# WallE_2_0.net
KiCad netlist of a schematic drawn in EAGLE
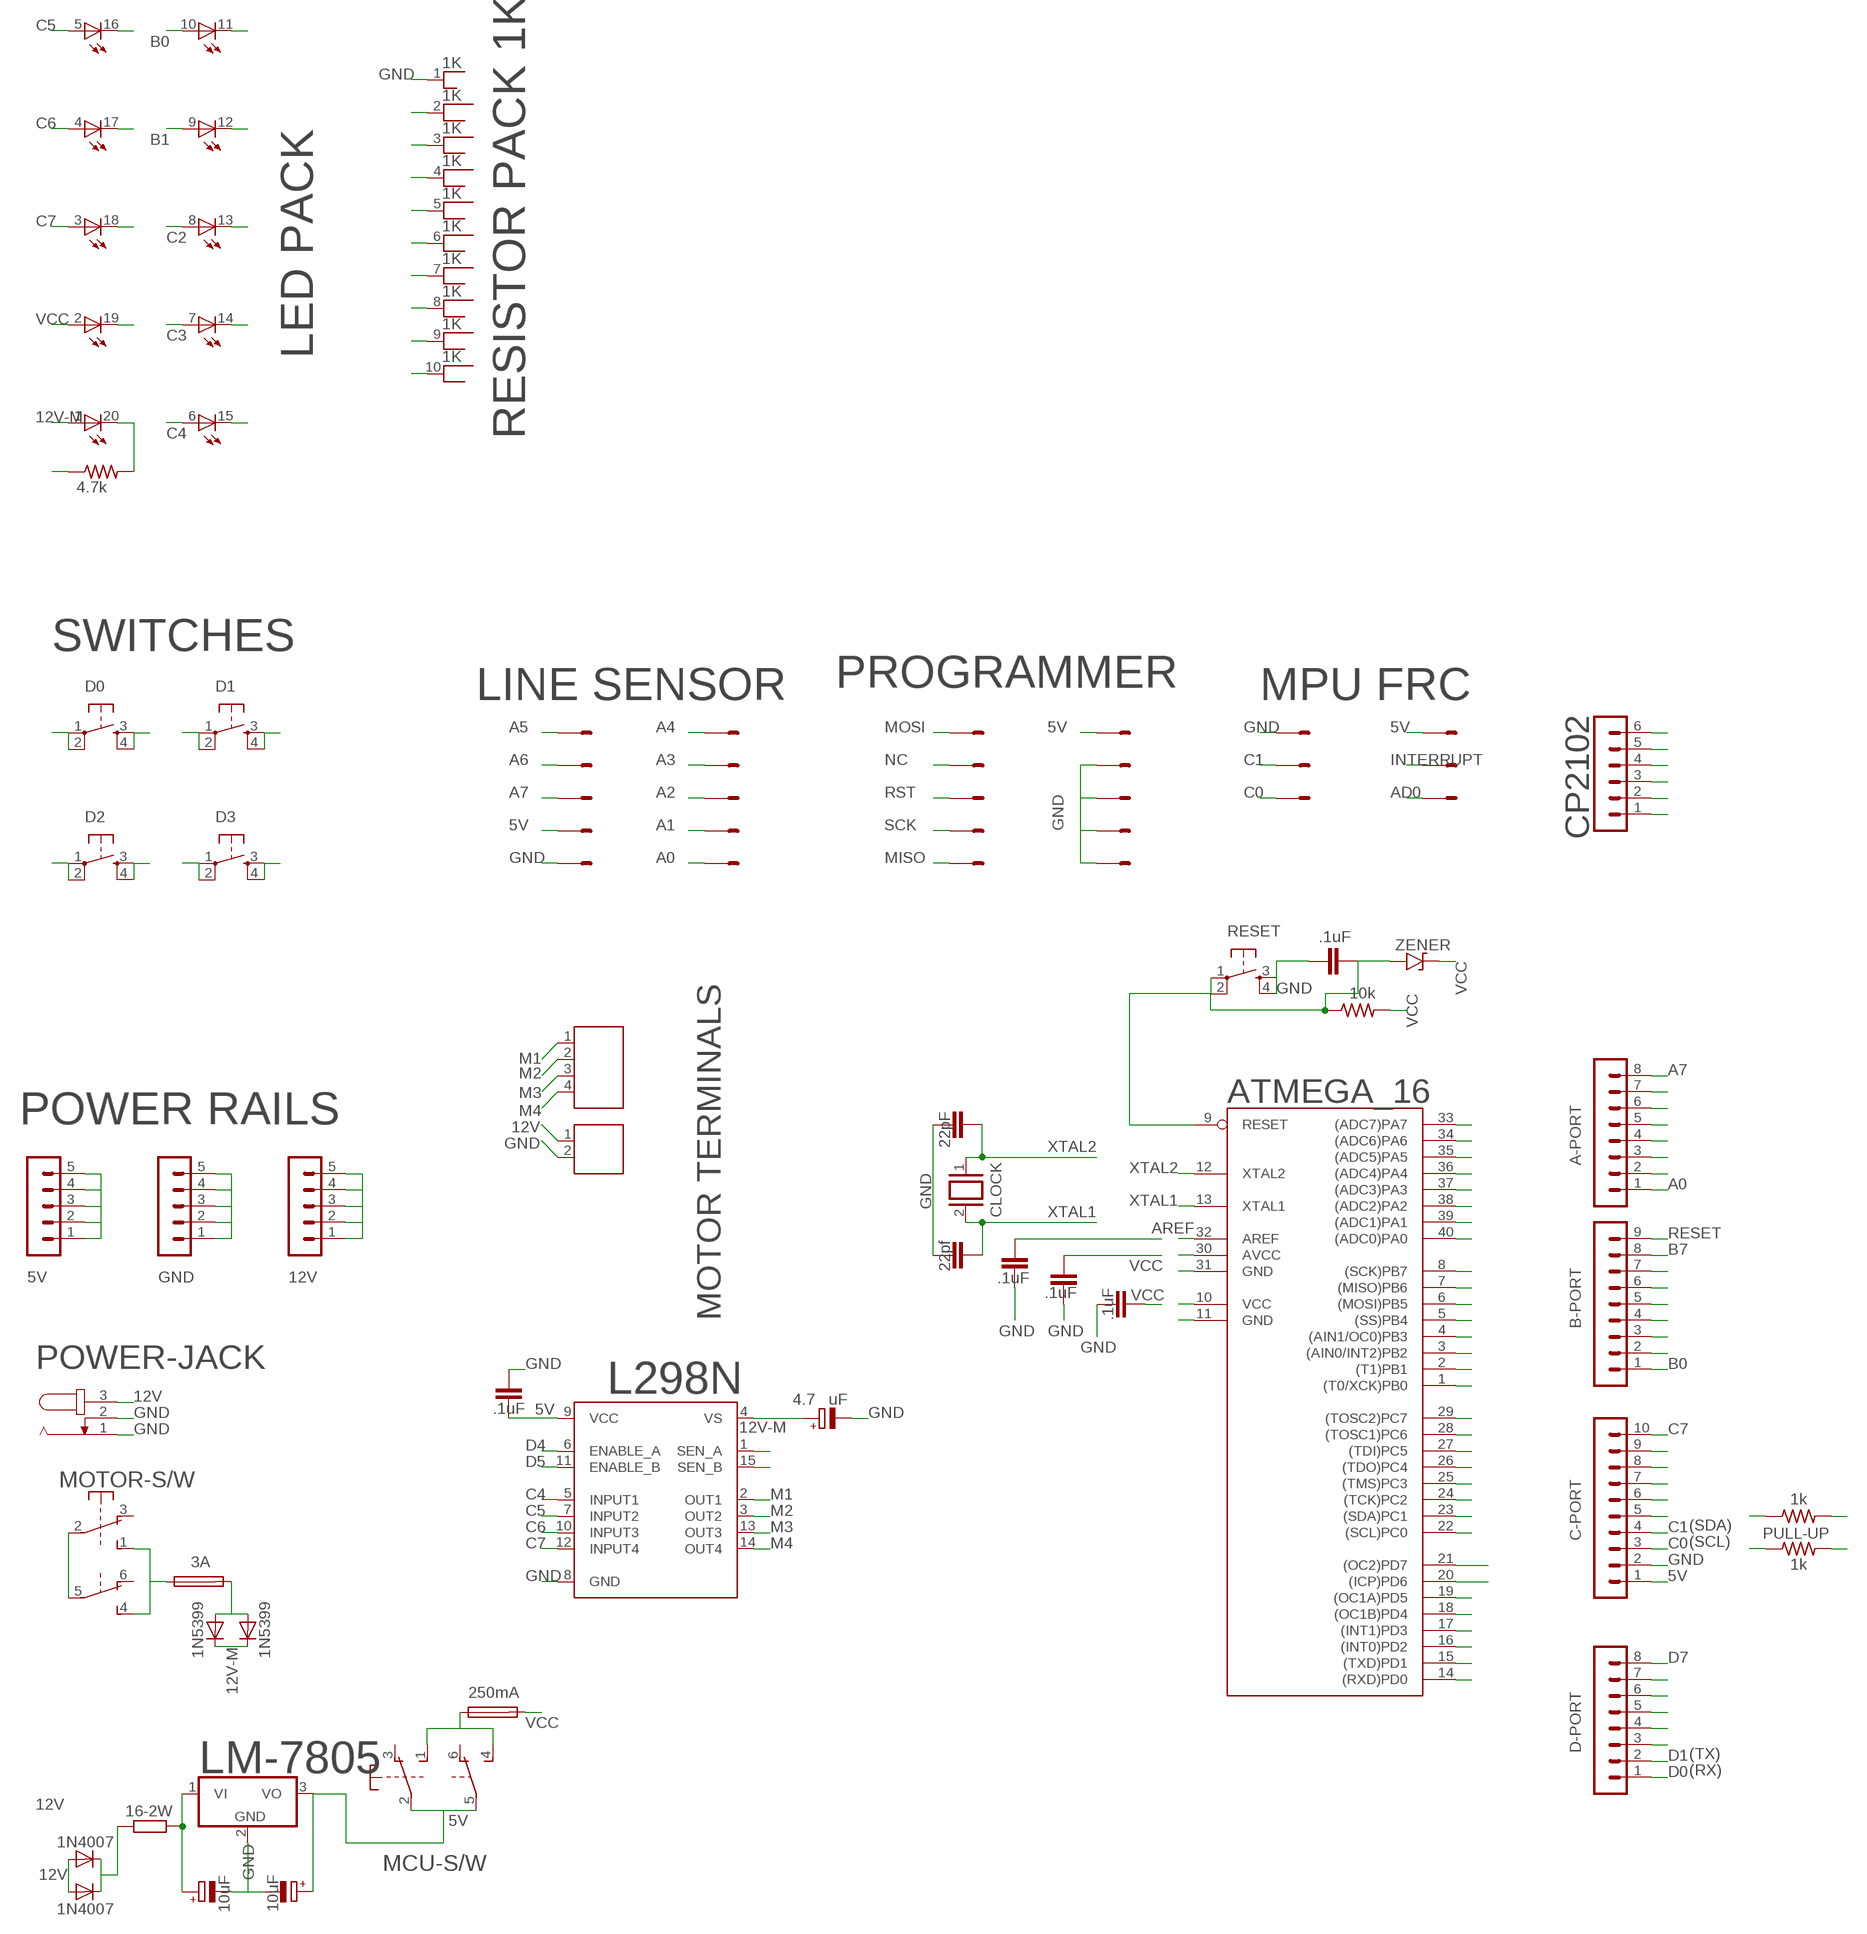
[diagram p0: schematic, sheet 1]

(export (version "E")
  (design (tool "Eeschema 10.0.6"))
  (components
    (comp (ref "5V")
      (value "MA05-1")
      (footprint "eagle-import:MA05-1")
      (libsource (lib "eagle-import") (part "MA05-1"))
    )
    (comp (ref "12V")
      (value "MA05-1")
      (footprint "eagle-import:MA05-1")
      (libsource (lib "eagle-import") (part "MA05-1"))
    )
    (comp (ref "16-2W")
      (value "R-EU_0617/17")
      (footprint "eagle-import:0617_17")
      (libsource (lib "eagle-import") (part "R-EU_0617/17"))
    )
    (comp (ref "A-PORT")
      (value "MA08-1")
      (footprint "eagle-import:MA08-1")
      (libsource (lib "eagle-import") (part "MA08-1"))
    )
    (comp (ref "ATMEGA_16")
      (value "MEGA32-P")
      (footprint "eagle-import:DIL40")
      (fields (field (name "MPN") "ATMEGA32-16PU"))
      (libsource (lib "eagle-import") (part "MEGA32-P"))
    )
    (comp (ref "B-PORT")
      (value "MA09-1")
      (footprint "eagle-import:MA09-1")
      (libsource (lib "eagle-import") (part "MA09-1"))
    )
    (comp (ref "C-PORT")
      (value "MA10-1")
      (footprint "eagle-import:MA10-1")
      (libsource (lib "eagle-import") (part "MA10-1"))
    )
    (comp (ref "C1")
      (value "10uF")
      (footprint "eagle-import:E2,5-6")
      (libsource (lib "eagle-import") (part "CPOL-EUE2.5-6"))
    )
    (comp (ref "C2")
      (value ".1uF")
      (footprint "eagle-import:C5B2.5")
      (libsource (lib "eagle-import") (part "C5/2.5"))
    )
    (comp (ref "C3")
      (value "22pf")
      (footprint "eagle-import:C2.5-2")
      (libsource (lib "eagle-import") (part "C2.5/2"))
    )
    (comp (ref "C4")
      (value "22pF")
      (footprint "eagle-import:C2.5-2")
      (libsource (lib "eagle-import") (part "C2.5/2"))
    )
    (comp (ref "C5")
      (value ".1uF")
      (footprint "eagle-import:C5B2.5")
      (libsource (lib "eagle-import") (part "C5/2.5"))
    )
    (comp (ref "C6")
      (value ".1uF")
      (footprint "eagle-import:C5B2.5")
      (libsource (lib "eagle-import") (part "C5/2.5"))
    )
    (comp (ref "C7")
      (value ".1uF")
      (footprint "eagle-import:C5B2.5")
      (libsource (lib "eagle-import") (part "C5/2.5"))
    )
    (comp (ref "C8")
      (value "4.7 uF")
      (footprint "eagle-import:E2,5-6")
      (libsource (lib "eagle-import") (part "CPOL-EUE2.5-6"))
    )
    (comp (ref "C9")
      (value ".1uF")
      (footprint "eagle-import:C5B2.5")
      (libsource (lib "eagle-import") (part "C5/2.5"))
    )
    (comp (ref "C10")
      (value "10uF")
      (footprint "eagle-import:E2,5-6")
      (libsource (lib "eagle-import") (part "CPOL-EUE2.5-6"))
    )
    (comp (ref "CLOCK")
      (value "XTAL/S")
      (footprint "eagle-import:QS")
      (libsource (lib "eagle-import") (part "XTAL/S"))
    )
    (comp (ref "CP2102")
      (value "MA06-1")
      (footprint "eagle-import:MA06-1")
      (libsource (lib "eagle-import") (part "MA06-1"))
    )
    (comp (ref "D-PORT")
      (value "MA08-1")
      (footprint "eagle-import:MA08-1")
      (libsource (lib "eagle-import") (part "MA08-1"))
    )
    (comp (ref "D0")
      (value "DTS-6")
      (footprint "eagle-import:DTS-6")
      (libsource (lib "eagle-import") (part "DTS-6"))
    )
    (comp (ref "D1")
      (value "DTS-6")
      (footprint "eagle-import:DTS-6")
      (libsource (lib "eagle-import") (part "DTS-6"))
    )
    (comp (ref "D2")
      (value "DTS-6")
      (footprint "eagle-import:DTS-6")
      (libsource (lib "eagle-import") (part "DTS-6"))
    )
    (comp (ref "D3")
      (value "DTS-6")
      (footprint "eagle-import:DTS-6")
      (libsource (lib "eagle-import") (part "DTS-6"))
    )
    (comp (ref "D4")
      (value "1N4007")
      (footprint "eagle-import:D-7.5")
      (libsource (lib "eagle-import") (part "DIODE-D-7.5"))
    )
    (comp (ref "D5")
      (value "1N4007")
      (footprint "eagle-import:D-7.5")
      (libsource (lib "eagle-import") (part "DIODE-D-7.5"))
    )
    (comp (ref "D6")
      (value "1N5399")
      (footprint "eagle-import:DO15-12")
      (libsource (lib "eagle-import") (part "DIODE-DO15-12"))
    )
    (comp (ref "D7")
      (value "1N5399")
      (footprint "eagle-import:DO15-12")
      (libsource (lib "eagle-import") (part "DIODE-DO15-12"))
    )
    (comp (ref "DZ1")
      (value "LB10")
      (footprint "eagle-import:LB10")
      (libsource (lib "eagle-import") (part "LB10"))
    )
    (comp (ref "F1")
      (value "3A")
      (footprint "eagle-import:SH25")
      (fields (field (name "MF") "SCHURTER") (field (name "MPN") "0031.8211"))
      (libsource (lib "eagle-import") (part "SH25"))
    )
    (comp (ref "F2")
      (value "250mA")
      (footprint "eagle-import:SH25")
      (fields (field (name "MF") "SCHURTER") (field (name "MPN") "0031.8211"))
      (libsource (lib "eagle-import") (part "SH25"))
    )
    (comp (ref "GND")
      (value "MA05-1")
      (footprint "eagle-import:MA05-1")
      (libsource (lib "eagle-import") (part "MA05-1"))
    )
    (comp (ref "J1")
      (value "691131710004")
      (footprint "eagle-import:691131710004")
      (libsource (lib "eagle-import") (part "691131710004"))
    )
    (comp (ref "J2")
      (value "691131710002")
      (footprint "eagle-import:691131710002")
      (libsource (lib "eagle-import") (part "691131710002"))
    )
    (comp (ref "L298N")
      (value "L298")
      (footprint "eagle-import:MULTIWATT-15")
      (fields (field (name "MPN") "L298N"))
      (libsource (lib "eagle-import") (part "L298"))
    )
    (comp (ref "LINE-SENSOR")
      (value "057-010-1")
      (footprint "eagle-import:057-010-1")
      (libsource (lib "eagle-import") (part "057-010-1"))
    )
    (comp (ref "LM-7805")
      (value "786TV")
      (footprint "eagle-import:TO220V")
      (libsource (lib "eagle-import") (part "78TV6"))
    )
    (comp (ref "MCU-S/W")
      (value "9077-2")
      (footprint "eagle-import:9077-2")
      (libsource (lib "eagle-import") (part "9077-2"))
    )
    (comp (ref "MOTOR-S/W")
      (value "9077-2")
      (footprint "eagle-import:9077-2")
      (libsource (lib "eagle-import") (part "9077-2"))
    )
    (comp (ref "MPU-6050")
      (value "057-006-1")
      (footprint "eagle-import:057-006-1")
      (libsource (lib "eagle-import") (part "057-006-1"))
    )
    (comp (ref "POWER-JACK")
      (value "JACK-PLUG1")
      (footprint "eagle-import:SPC4078")
      (libsource (lib "eagle-import") (part "JACK-PLUG1"))
    )
    (comp (ref "R2")
      (value "4.7k")
      (footprint "eagle-import:0207_7")
      (libsource (lib "eagle-import") (part "R-US_0207/7"))
    )
    (comp (ref "R3")
      (value "10k")
      (footprint "eagle-import:0207_7")
      (libsource (lib "eagle-import") (part "R-US_0207/7"))
    )
    (comp (ref "R5")
      (value "1k")
      (footprint "eagle-import:0207_7")
      (libsource (lib "eagle-import") (part "R-US_0207/7"))
    )
    (comp (ref "R6")
      (value "1k")
      (footprint "eagle-import:0207_7")
      (libsource (lib "eagle-import") (part "R-US_0207/7"))
    )
    (comp (ref "RESET")
      (value "DTS-6")
      (footprint "eagle-import:DTS-6")
      (libsource (lib "eagle-import") (part "DTS-6"))
    )
    (comp (ref "RN1")
      (value "1K")
      (footprint "eagle-import:RN-10")
      (libsource (lib "eagle-import") (part "RNX9"))
    )
    (comp (ref "X2")
      (value "PROGRAMMER")
      (footprint "eagle-import:057-010-1")
      (libsource (lib "eagle-import") (part "057-010-1"))
    )
    (comp (ref "ZENER")
      (value "ZENER")
      (footprint "eagle-import:DO35-2")
      (libsource (lib "eagle-import") (part "1N9ZENER2"))
    )
  )
  (nets
    (net (code "1") (name "/5V") (class "Default")
      (node (ref "5V") (pin "1") (pinfunction "1_1") (pintype "passive"))
      (node (ref "5V") (pin "2") (pinfunction "2_2") (pintype "passive"))
      (node (ref "5V") (pin "3") (pinfunction "3_3") (pintype "passive"))
      (node (ref "5V") (pin "4") (pinfunction "4_4") (pintype "passive"))
      (node (ref "5V") (pin "5") (pinfunction "5_5") (pintype "passive"))
      (node (ref "C-PORT") (pin "1") (pinfunction "1_1") (pintype "passive"))
      (node (ref "C10") (pin "+") (pinfunction "+_+") (pintype "passive"))
      (node (ref "C9") (pin "1") (pinfunction "1_1") (pintype "passive"))
      (node (ref "CP2102") (pin "6") (pinfunction "6_6") (pintype "passive"))
      (node (ref "L298N") (pin "9") (pinfunction "VCC_9") (pintype "power_in"))
      (node (ref "LINE-SENSOR") (pin "7") (pinfunction "S_7") (pintype "passive"))
      (node (ref "LM-7805") (pin "3") (pinfunction "VO_3") (pintype "passive"))
      (node (ref "MCU-S/W") (pin "2") (pinfunction "P_2") (pintype "passive"))
      (node (ref "MCU-S/W") (pin "5") (pinfunction "P_5") (pintype "passive"))
      (node (ref "MPU-6050") (pin "2") (pinfunction "S_2") (pintype "passive"))
      (node (ref "R5") (pin "2") (pinfunction "2_2") (pintype "passive"))
      (node (ref "R6") (pin "2") (pinfunction "2_2") (pintype "passive"))
      (node (ref "X2") (pin "2") (pinfunction "S_2") (pintype "passive"))
    )
    (net (code "2") (name "/12V") (class "Default")
      (node (ref "12V") (pin "1") (pinfunction "1_1") (pintype "passive"))
      (node (ref "12V") (pin "2") (pinfunction "2_2") (pintype "passive"))
      (node (ref "12V") (pin "3") (pinfunction "3_3") (pintype "passive"))
      (node (ref "12V") (pin "4") (pinfunction "4_4") (pintype "passive"))
      (node (ref "12V") (pin "5") (pinfunction "5_5") (pintype "passive"))
      (node (ref "D4") (pin "A") (pinfunction "A_A") (pintype "passive"))
      (node (ref "D5") (pin "A") (pinfunction "A_A") (pintype "passive"))
      (node (ref "J2") (pin "1") (pinfunction "1_1") (pintype "passive"))
      (node (ref "MOTOR-S/W") (pin "2") (pinfunction "P_2") (pintype "passive"))
      (node (ref "MOTOR-S/W") (pin "5") (pinfunction "P_5") (pintype "passive"))
      (node (ref "POWER-JACK") (pin "3") (pinfunction "3_3") (pintype "passive"))
    )
    (net (code "3") (name "/12V-M") (class "Default")
      (node (ref "C8") (pin "+") (pinfunction "+_+") (pintype "passive"))
      (node (ref "D6") (pin "C") (pinfunction "C_C") (pintype "passive"))
      (node (ref "D7") (pin "C") (pinfunction "C_C") (pintype "passive"))
      (node (ref "DZ1") (pin "1") (pinfunction "A_1") (pintype "passive"))
      (node (ref "L298N") (pin "4") (pinfunction "VS_4") (pintype "power_in"))
    )
    (net (code "4") (name "/A0") (class "Default")
      (node (ref "A-PORT") (pin "1") (pinfunction "1_1") (pintype "passive"))
      (node (ref "ATMEGA_16") (pin "40") (pinfunction "(ADC0)PA0_40") (pintype "bidirectional"))
      (node (ref "LINE-SENSOR") (pin "10") (pinfunction "S_10") (pintype "passive"))
    )
    (net (code "5") (name "/A1") (class "Default")
      (node (ref "A-PORT") (pin "2") (pinfunction "2_2") (pintype "passive"))
      (node (ref "ATMEGA_16") (pin "39") (pinfunction "(ADC1)PA1_39") (pintype "bidirectional"))
      (node (ref "LINE-SENSOR") (pin "8") (pinfunction "S_8") (pintype "passive"))
    )
    (net (code "6") (name "/A2") (class "Default")
      (node (ref "A-PORT") (pin "3") (pinfunction "3_3") (pintype "passive"))
      (node (ref "ATMEGA_16") (pin "38") (pinfunction "(ADC2)PA2_38") (pintype "bidirectional"))
      (node (ref "LINE-SENSOR") (pin "6") (pinfunction "S_6") (pintype "passive"))
    )
    (net (code "7") (name "/A3") (class "Default")
      (node (ref "A-PORT") (pin "4") (pinfunction "4_4") (pintype "passive"))
      (node (ref "ATMEGA_16") (pin "37") (pinfunction "(ADC3)PA3_37") (pintype "bidirectional"))
      (node (ref "LINE-SENSOR") (pin "4") (pinfunction "S_4") (pintype "passive"))
    )
    (net (code "8") (name "/A4") (class "Default")
      (node (ref "A-PORT") (pin "5") (pinfunction "5_5") (pintype "passive"))
      (node (ref "ATMEGA_16") (pin "36") (pinfunction "(ADC4)PA4_36") (pintype "bidirectional"))
      (node (ref "LINE-SENSOR") (pin "2") (pinfunction "S_2") (pintype "passive"))
    )
    (net (code "9") (name "/A5") (class "Default")
      (node (ref "A-PORT") (pin "6") (pinfunction "6_6") (pintype "passive"))
      (node (ref "ATMEGA_16") (pin "35") (pinfunction "(ADC5)PA5_35") (pintype "bidirectional"))
      (node (ref "LINE-SENSOR") (pin "1") (pinfunction "S_1") (pintype "passive"))
    )
    (net (code "10") (name "/A6") (class "Default")
      (node (ref "A-PORT") (pin "7") (pinfunction "7_7") (pintype "passive"))
      (node (ref "ATMEGA_16") (pin "34") (pinfunction "(ADC6)PA6_34") (pintype "bidirectional"))
      (node (ref "LINE-SENSOR") (pin "3") (pinfunction "S_3") (pintype "passive"))
    )
    (net (code "11") (name "/A7") (class "Default")
      (node (ref "A-PORT") (pin "8") (pinfunction "8_8") (pintype "passive"))
      (node (ref "ATMEGA_16") (pin "33") (pinfunction "(ADC7)PA7_33") (pintype "bidirectional"))
      (node (ref "LINE-SENSOR") (pin "5") (pinfunction "S_5") (pintype "passive"))
    )
    (net (code "12") (name "/AREF") (class "Default")
      (node (ref "ATMEGA_16") (pin "32") (pinfunction "AREF_32") (pintype "passive"))
      (node (ref "C7") (pin "1") (pinfunction "1_1") (pintype "passive"))
    )
    (net (code "13") (name "/B0") (class "Default")
      (node (ref "ATMEGA_16") (pin "1") (pinfunction "(T0/XCK)PB0_1") (pintype "bidirectional"))
      (node (ref "B-PORT") (pin "1") (pinfunction "1_1") (pintype "passive"))
      (node (ref "DZ1") (pin "10") (pinfunction "A_10") (pintype "passive"))
    )
    (net (code "14") (name "/B0R") (class "Default")
      (node (ref "DZ1") (pin "11") (pinfunction "C_11") (pintype "passive"))
      (node (ref "RN1") (pin "10") (pinfunction "1_10") (pintype "passive"))
    )
    (net (code "15") (name "/B1") (class "Default")
      (node (ref "ATMEGA_16") (pin "2") (pinfunction "(T1)PB1_2") (pintype "bidirectional"))
      (node (ref "B-PORT") (pin "2") (pinfunction "2_2") (pintype "passive"))
      (node (ref "DZ1") (pin "9") (pinfunction "A_9") (pintype "passive"))
    )
    (net (code "16") (name "/B1R") (class "Default")
      (node (ref "DZ1") (pin "12") (pinfunction "C_12") (pintype "passive"))
      (node (ref "RN1") (pin "9") (pinfunction "1_9") (pintype "passive"))
    )
    (net (code "17") (name "/B2") (class "Default")
      (node (ref "ATMEGA_16") (pin "3") (pinfunction "(AIN0/INT2)PB2_3") (pintype "bidirectional"))
      (node (ref "B-PORT") (pin "3") (pinfunction "3_3") (pintype "passive"))
    )
    (net (code "18") (name "/B3") (class "Default")
      (node (ref "ATMEGA_16") (pin "4") (pinfunction "(AIN1/OC0)PB3_4") (pintype "bidirectional"))
      (node (ref "B-PORT") (pin "4") (pinfunction "4_4") (pintype "passive"))
    )
    (net (code "19") (name "/B4") (class "Default")
      (node (ref "ATMEGA_16") (pin "5") (pinfunction "(SS)PB4_5") (pintype "bidirectional"))
      (node (ref "B-PORT") (pin "5") (pinfunction "5_5") (pintype "passive"))
    )
    (net (code "20") (name "/B5") (class "Default")
      (node (ref "ATMEGA_16") (pin "6") (pinfunction "(MOSI)PB5_6") (pintype "bidirectional"))
      (node (ref "B-PORT") (pin "6") (pinfunction "6_6") (pintype "passive"))
      (node (ref "X2") (pin "1") (pinfunction "S_1") (pintype "passive"))
    )
    (net (code "21") (name "/B6") (class "Default")
      (node (ref "ATMEGA_16") (pin "7") (pinfunction "(MISO)PB6_7") (pintype "bidirectional"))
      (node (ref "B-PORT") (pin "7") (pinfunction "7_7") (pintype "passive"))
      (node (ref "X2") (pin "9") (pinfunction "S_9") (pintype "passive"))
    )
    (net (code "22") (name "/B7") (class "Default")
      (node (ref "ATMEGA_16") (pin "8") (pinfunction "(SCK)PB7_8") (pintype "bidirectional"))
      (node (ref "B-PORT") (pin "8") (pinfunction "8_8") (pintype "passive"))
      (node (ref "X2") (pin "7") (pinfunction "S_7") (pintype "passive"))
    )
    (net (code "23") (name "/C0") (class "Default")
      (node (ref "ATMEGA_16") (pin "22") (pinfunction "(SCL)PC0_22") (pintype "bidirectional"))
      (node (ref "C-PORT") (pin "3") (pinfunction "3_3") (pintype "passive"))
      (node (ref "MPU-6050") (pin "5") (pinfunction "S_5") (pintype "passive"))
      (node (ref "R6") (pin "1") (pinfunction "1_1") (pintype "passive"))
    )
    (net (code "24") (name "/C1") (class "Default")
      (node (ref "ATMEGA_16") (pin "23") (pinfunction "(SDA)PC1_23") (pintype "bidirectional"))
      (node (ref "C-PORT") (pin "4") (pinfunction "4_4") (pintype "passive"))
      (node (ref "MPU-6050") (pin "3") (pinfunction "S_3") (pintype "passive"))
      (node (ref "R5") (pin "1") (pinfunction "1_1") (pintype "passive"))
    )
    (net (code "25") (name "/C2") (class "Default")
      (node (ref "ATMEGA_16") (pin "24") (pinfunction "(TCK)PC2_24") (pintype "bidirectional"))
      (node (ref "C-PORT") (pin "5") (pinfunction "5_5") (pintype "passive"))
      (node (ref "DZ1") (pin "8") (pinfunction "A_8") (pintype "passive"))
    )
    (net (code "26") (name "/C2R") (class "Default")
      (node (ref "DZ1") (pin "13") (pinfunction "C_13") (pintype "passive"))
      (node (ref "RN1") (pin "8") (pinfunction "1_8") (pintype "passive"))
    )
    (net (code "27") (name "/C3") (class "Default")
      (node (ref "ATMEGA_16") (pin "25") (pinfunction "(TMS)PC3_25") (pintype "bidirectional"))
      (node (ref "C-PORT") (pin "6") (pinfunction "6_6") (pintype "passive"))
      (node (ref "DZ1") (pin "7") (pinfunction "A_7") (pintype "passive"))
    )
    (net (code "28") (name "/C3R") (class "Default")
      (node (ref "DZ1") (pin "14") (pinfunction "C_14") (pintype "passive"))
      (node (ref "RN1") (pin "7") (pinfunction "1_7") (pintype "passive"))
    )
    (net (code "29") (name "/C4") (class "Default")
      (node (ref "ATMEGA_16") (pin "26") (pinfunction "(TDO)PC4_26") (pintype "bidirectional"))
      (node (ref "C-PORT") (pin "7") (pinfunction "7_7") (pintype "passive"))
      (node (ref "DZ1") (pin "6") (pinfunction "A_6") (pintype "passive"))
      (node (ref "L298N") (pin "5") (pinfunction "INPUT1_5") (pintype "input"))
    )
    (net (code "30") (name "/C4R") (class "Default")
      (node (ref "DZ1") (pin "15") (pinfunction "C_15") (pintype "passive"))
      (node (ref "RN1") (pin "6") (pinfunction "1_6") (pintype "passive"))
    )
    (net (code "31") (name "/C5") (class "Default")
      (node (ref "ATMEGA_16") (pin "27") (pinfunction "(TDI)PC5_27") (pintype "bidirectional"))
      (node (ref "C-PORT") (pin "8") (pinfunction "8_8") (pintype "passive"))
      (node (ref "DZ1") (pin "5") (pinfunction "A_5") (pintype "passive"))
      (node (ref "L298N") (pin "7") (pinfunction "INPUT2_7") (pintype "input"))
    )
    (net (code "32") (name "/C5R") (class "Default")
      (node (ref "DZ1") (pin "16") (pinfunction "C_16") (pintype "passive"))
      (node (ref "RN1") (pin "5") (pinfunction "1_5") (pintype "passive"))
    )
    (net (code "33") (name "/C6") (class "Default")
      (node (ref "ATMEGA_16") (pin "28") (pinfunction "(TOSC1)PC6_28") (pintype "bidirectional"))
      (node (ref "C-PORT") (pin "9") (pinfunction "9_9") (pintype "passive"))
      (node (ref "DZ1") (pin "4") (pinfunction "A_4") (pintype "passive"))
      (node (ref "L298N") (pin "10") (pinfunction "INPUT3_10") (pintype "input"))
    )
    (net (code "34") (name "/C6R") (class "Default")
      (node (ref "DZ1") (pin "17") (pinfunction "C_17") (pintype "passive"))
      (node (ref "RN1") (pin "4") (pinfunction "1_4") (pintype "passive"))
    )
    (net (code "35") (name "/C7") (class "Default")
      (node (ref "ATMEGA_16") (pin "29") (pinfunction "(TOSC2)PC7_29") (pintype "bidirectional"))
      (node (ref "C-PORT") (pin "10") (pinfunction "10_10") (pintype "passive"))
      (node (ref "DZ1") (pin "3") (pinfunction "A_3") (pintype "passive"))
      (node (ref "L298N") (pin "12") (pinfunction "INPUT4_12") (pintype "input"))
    )
    (net (code "36") (name "/C7R") (class "Default")
      (node (ref "DZ1") (pin "18") (pinfunction "C_18") (pintype "passive"))
      (node (ref "RN1") (pin "3") (pinfunction "1_3") (pintype "passive"))
    )
    (net (code "37") (name "/D0") (class "Default")
      (node (ref "ATMEGA_16") (pin "14") (pinfunction "(RXD)PD0_14") (pintype "bidirectional"))
      (node (ref "CP2102") (pin "3") (pinfunction "3_3") (pintype "passive"))
      (node (ref "D-PORT") (pin "1") (pinfunction "1_1") (pintype "passive"))
      (node (ref "D0") (pin "1") (pinfunction "1_1") (pintype "passive"))
      (node (ref "D0") (pin "2") (pinfunction "2_2") (pintype "passive"))
    )
    (net (code "38") (name "/D1") (class "Default")
      (node (ref "ATMEGA_16") (pin "15") (pinfunction "(TXD)PD1_15") (pintype "bidirectional"))
      (node (ref "CP2102") (pin "4") (pinfunction "4_4") (pintype "passive"))
      (node (ref "D-PORT") (pin "2") (pinfunction "2_2") (pintype "passive"))
      (node (ref "D1") (pin "1") (pinfunction "1_1") (pintype "passive"))
      (node (ref "D1") (pin "2") (pinfunction "2_2") (pintype "passive"))
    )
    (net (code "39") (name "/D2") (class "Default")
      (node (ref "ATMEGA_16") (pin "16") (pinfunction "(INT0)PD2_16") (pintype "bidirectional"))
      (node (ref "D-PORT") (pin "3") (pinfunction "3_3") (pintype "passive"))
      (node (ref "D2") (pin "1") (pinfunction "1_1") (pintype "passive"))
      (node (ref "D2") (pin "2") (pinfunction "2_2") (pintype "passive"))
    )
    (net (code "40") (name "/D3") (class "Default")
      (node (ref "ATMEGA_16") (pin "17") (pinfunction "(INT1)PD3_17") (pintype "bidirectional"))
      (node (ref "D-PORT") (pin "4") (pinfunction "4_4") (pintype "passive"))
      (node (ref "D3") (pin "1") (pinfunction "1_1") (pintype "passive"))
      (node (ref "D3") (pin "2") (pinfunction "2_2") (pintype "passive"))
    )
    (net (code "41") (name "/D4") (class "Default")
      (node (ref "ATMEGA_16") (pin "18") (pinfunction "(OC1B)PD4_18") (pintype "bidirectional"))
      (node (ref "D-PORT") (pin "5") (pinfunction "5_5") (pintype "passive"))
      (node (ref "L298N") (pin "6") (pinfunction "ENABLE_A_6") (pintype "input"))
    )
    (net (code "42") (name "/D5") (class "Default")
      (node (ref "ATMEGA_16") (pin "19") (pinfunction "(OC1A)PD5_19") (pintype "bidirectional"))
      (node (ref "D-PORT") (pin "6") (pinfunction "6_6") (pintype "passive"))
      (node (ref "L298N") (pin "11") (pinfunction "ENABLE_B_11") (pintype "input"))
    )
    (net (code "43") (name "/D6") (class "Default")
      (node (ref "ATMEGA_16") (pin "20") (pinfunction "(ICP)PD6_20") (pintype "bidirectional"))
      (node (ref "D-PORT") (pin "7") (pinfunction "7_7") (pintype "passive"))
    )
    (net (code "44") (name "/D7") (class "Default")
      (node (ref "ATMEGA_16") (pin "21") (pinfunction "(OC2)PD7_21") (pintype "bidirectional"))
      (node (ref "D-PORT") (pin "8") (pinfunction "8_8") (pintype "passive"))
    )
    (net (code "45") (name "/GND") (class "Default")
      (node (ref "ATMEGA_16") (pin "11") (pinfunction "GND_11") (pintype "power_in"))
      (node (ref "ATMEGA_16") (pin "31") (pinfunction "GND_31") (pintype "power_in"))
      (node (ref "C-PORT") (pin "2") (pinfunction "2_2") (pintype "passive"))
      (node (ref "C1") (pin "-") (pinfunction "-_-") (pintype "passive"))
      (node (ref "C10") (pin "-") (pinfunction "-_-") (pintype "passive"))
      (node (ref "C2") (pin "2") (pinfunction "2_2") (pintype "passive"))
      (node (ref "C3") (pin "2") (pinfunction "2_2") (pintype "passive"))
      (node (ref "C4") (pin "2") (pinfunction "2_2") (pintype "passive"))
      (node (ref "C5") (pin "2") (pinfunction "2_2") (pintype "passive"))
      (node (ref "C6") (pin "2") (pinfunction "2_2") (pintype "passive"))
      (node (ref "C7") (pin "2") (pinfunction "2_2") (pintype "passive"))
      (node (ref "C8") (pin "-") (pinfunction "-_-") (pintype "passive"))
      (node (ref "C9") (pin "2") (pinfunction "2_2") (pintype "passive"))
      (node (ref "CP2102") (pin "5") (pinfunction "5_5") (pintype "passive"))
      (node (ref "D0") (pin "3") (pinfunction "3_3") (pintype "passive"))
      (node (ref "D0") (pin "4") (pinfunction "4_4") (pintype "passive"))
      (node (ref "D1") (pin "3") (pinfunction "3_3") (pintype "passive"))
      (node (ref "D1") (pin "4") (pinfunction "4_4") (pintype "passive"))
      (node (ref "D2") (pin "3") (pinfunction "3_3") (pintype "passive"))
      (node (ref "D2") (pin "4") (pinfunction "4_4") (pintype "passive"))
      (node (ref "D3") (pin "3") (pinfunction "3_3") (pintype "passive"))
      (node (ref "D3") (pin "4") (pinfunction "4_4") (pintype "passive"))
      (node (ref "GND") (pin "1") (pinfunction "1_1") (pintype "passive"))
      (node (ref "GND") (pin "2") (pinfunction "2_2") (pintype "passive"))
      (node (ref "GND") (pin "3") (pinfunction "3_3") (pintype "passive"))
      (node (ref "GND") (pin "4") (pinfunction "4_4") (pintype "passive"))
      (node (ref "GND") (pin "5") (pinfunction "5_5") (pintype "passive"))
      (node (ref "J2") (pin "2") (pinfunction "2_2") (pintype "passive"))
      (node (ref "L298N") (pin "1") (pinfunction "SEN_A_1") (pintype "input"))
      (node (ref "L298N") (pin "15") (pinfunction "SEN_B_15") (pintype "input"))
      (node (ref "L298N") (pin "8") (pinfunction "GND_8") (pintype "power_in"))
      (node (ref "LINE-SENSOR") (pin "9") (pinfunction "S_9") (pintype "passive"))
      (node (ref "LM-7805") (pin "2") (pinfunction "GND_2") (pintype "passive"))
      (node (ref "MPU-6050") (pin "1") (pinfunction "S_1") (pintype "passive"))
      (node (ref "MPU-6050") (pin "6") (pinfunction "S_6") (pintype "passive"))
      (node (ref "POWER-JACK") (pin "1") (pinfunction "1_1") (pintype "passive"))
      (node (ref "POWER-JACK") (pin "2") (pinfunction "2_2") (pintype "passive"))
      (node (ref "R2") (pin "1") (pinfunction "1_1") (pintype "passive"))
      (node (ref "RESET") (pin "3") (pinfunction "3_3") (pintype "passive"))
      (node (ref "RESET") (pin "4") (pinfunction "4_4") (pintype "passive"))
      (node (ref "RN1") (pin "1") (pinfunction "1_1") (pintype "passive"))
      (node (ref "X2") (pin "10") (pinfunction "S_10") (pintype "passive"))
      (node (ref "X2") (pin "4") (pinfunction "S_4") (pintype "passive"))
      (node (ref "X2") (pin "6") (pinfunction "S_6") (pintype "passive"))
      (node (ref "X2") (pin "8") (pinfunction "S_8") (pintype "passive"))
    )
    (net (code "46") (name "/INTERRUPT") (class "Default")
      (node (ref "MPU-6050") (pin "4") (pinfunction "S_4") (pintype "passive"))
    )
    (net (code "47") (name "/M1") (class "Default")
      (node (ref "J1") (pin "1") (pinfunction "1_1") (pintype "passive"))
      (node (ref "L298N") (pin "2") (pinfunction "OUT1_2") (pintype "output"))
    )
    (net (code "48") (name "/M2") (class "Default")
      (node (ref "J1") (pin "2") (pinfunction "2_2") (pintype "passive"))
      (node (ref "L298N") (pin "3") (pinfunction "OUT2_3") (pintype "output"))
    )
    (net (code "49") (name "/M3") (class "Default")
      (node (ref "J1") (pin "3") (pinfunction "3_3") (pintype "passive"))
      (node (ref "L298N") (pin "13") (pinfunction "OUT3_13") (pintype "output"))
    )
    (net (code "50") (name "/M4") (class "Default")
      (node (ref "J1") (pin "4") (pinfunction "4_4") (pintype "passive"))
      (node (ref "L298N") (pin "14") (pinfunction "OUT4_14") (pintype "output"))
    )
    (net (code "51") (name "/RESET") (class "Default")
      (node (ref "ATMEGA_16") (pin "9") (pinfunction "RESET_9") (pintype "input"))
      (node (ref "B-PORT") (pin "9") (pinfunction "9_9") (pintype "passive"))
      (node (ref "C5") (pin "1") (pinfunction "1_1") (pintype "passive"))
      (node (ref "R3") (pin "1") (pinfunction "1_1") (pintype "passive"))
      (node (ref "RESET") (pin "1") (pinfunction "1_1") (pintype "passive"))
      (node (ref "RESET") (pin "2") (pinfunction "2_2") (pintype "passive"))
      (node (ref "X2") (pin "5") (pinfunction "S_5") (pintype "passive"))
      (node (ref "ZENER") (pin "A") (pinfunction "A_A") (pintype "passive"))
    )
    (net (code "52") (name "/VCC") (class "Default")
      (node (ref "ATMEGA_16") (pin "10") (pinfunction "VCC_10") (pintype "power_in"))
      (node (ref "ATMEGA_16") (pin "30") (pinfunction "AVCC_30") (pintype "power_in"))
      (node (ref "C2") (pin "1") (pinfunction "1_1") (pintype "passive"))
      (node (ref "C6") (pin "1") (pinfunction "1_1") (pintype "passive"))
      (node (ref "DZ1") (pin "2") (pinfunction "A_2") (pintype "passive"))
      (node (ref "F2") (pin "2") (pinfunction "2_2") (pintype "passive"))
      (node (ref "R3") (pin "2") (pinfunction "2_2") (pintype "passive"))
      (node (ref "ZENER") (pin "C") (pinfunction "C_C") (pintype "passive"))
    )
    (net (code "53") (name "/VCCR") (class "Default")
      (node (ref "DZ1") (pin "19") (pinfunction "C_19") (pintype "passive"))
      (node (ref "RN1") (pin "2") (pinfunction "1_2") (pintype "passive"))
    )
    (net (code "54") (name "/XTAL1") (class "Default")
      (node (ref "ATMEGA_16") (pin "13") (pinfunction "XTAL1_13") (pintype "bidirectional"))
      (node (ref "C3") (pin "1") (pinfunction "1_1") (pintype "passive"))
      (node (ref "CLOCK") (pin "2") (pinfunction "2_2") (pintype "passive"))
    )
    (net (code "55") (name "/XTAL2") (class "Default")
      (node (ref "ATMEGA_16") (pin "12") (pinfunction "XTAL2_12") (pintype "bidirectional"))
      (node (ref "C4") (pin "1") (pinfunction "1_1") (pintype "passive"))
      (node (ref "CLOCK") (pin "1") (pinfunction "1_1") (pintype "passive"))
    )
    (net (code "56") (name "Net-(16-2W-Pad1)") (class "Default")
      (node (ref "16-2W") (pin "1") (pinfunction "1_1") (pintype "passive"))
      (node (ref "D4") (pin "C") (pinfunction "C_C") (pintype "passive"))
      (node (ref "D5") (pin "C") (pinfunction "C_C") (pintype "passive"))
    )
    (net (code "57") (name "Net-(D6-PadA)") (class "Default")
      (node (ref "D6") (pin "A") (pinfunction "A_A") (pintype "passive"))
      (node (ref "D7") (pin "A") (pinfunction "A_A") (pintype "passive"))
      (node (ref "F1") (pin "2") (pinfunction "2_2") (pintype "passive"))
    )
    (net (code "58") (name "Net-(DZ1A-C)") (class "Default")
      (node (ref "DZ1") (pin "20") (pinfunction "C_20") (pintype "passive"))
      (node (ref "R2") (pin "2") (pinfunction "2_2") (pintype "passive"))
    )
    (net (code "59") (name "Net-(LM-7805-VI)") (class "Default")
      (node (ref "16-2W") (pin "2") (pinfunction "2_2") (pintype "passive"))
      (node (ref "C1") (pin "+") (pinfunction "+_+") (pintype "passive"))
      (node (ref "LM-7805") (pin "1") (pinfunction "VI_1") (pintype "input"))
    )
    (net (code "60") (name "Net-(MCU-S/WA-S)") (class "Default")
      (node (ref "F2") (pin "1") (pinfunction "1_1") (pintype "passive"))
      (node (ref "MCU-S/W") (pin "1") (pinfunction "S_1") (pintype "passive"))
      (node (ref "MCU-S/W") (pin "4") (pinfunction "S_4") (pintype "passive"))
    )
    (net (code "61") (name "Net-(MOTOR-S/WA-S)") (class "Default")
      (node (ref "F1") (pin "1") (pinfunction "1_1") (pintype "passive"))
      (node (ref "MOTOR-S/W") (pin "1") (pinfunction "S_1") (pintype "passive"))
      (node (ref "MOTOR-S/W") (pin "4") (pinfunction "S_4") (pintype "passive"))
    )
    (net (code "62") (name "unconnected-(CP2102-Pad1)") (class "Default")
      (node (ref "CP2102") (pin "1") (pinfunction "1_1") (pintype "passive"))
    )
    (net (code "63") (name "unconnected-(CP2102-Pad2)") (class "Default")
      (node (ref "CP2102") (pin "2") (pinfunction "2_2") (pintype "passive"))
    )
    (net (code "64") (name "unconnected-(MCU-S/WA-O-Pad3)") (class "Default")
      (node (ref "MCU-S/W") (pin "3") (pinfunction "O_3") (pintype "passive"))
    )
    (net (code "65") (name "unconnected-(MCU-S/WB-O-Pad6)") (class "Default")
      (node (ref "MCU-S/W") (pin "6") (pinfunction "O_6") (pintype "passive"))
    )
    (net (code "66") (name "unconnected-(MOTOR-S/WA-O-Pad3)") (class "Default")
      (node (ref "MOTOR-S/W") (pin "3") (pinfunction "O_3") (pintype "passive"))
    )
    (net (code "67") (name "unconnected-(MOTOR-S/WB-O-Pad6)") (class "Default")
      (node (ref "MOTOR-S/W") (pin "6") (pinfunction "O_6") (pintype "passive"))
    )
    (net (code "68") (name "unconnected-(X2D-S-Pad3)") (class "Default")
      (node (ref "X2") (pin "3") (pinfunction "S_3") (pintype "passive"))
    )
  )
)
